# SAMV71_Xplained_Ultra_MCU_Peripherals.net
KiCad netlist of a schematic drawn in Altium Designer
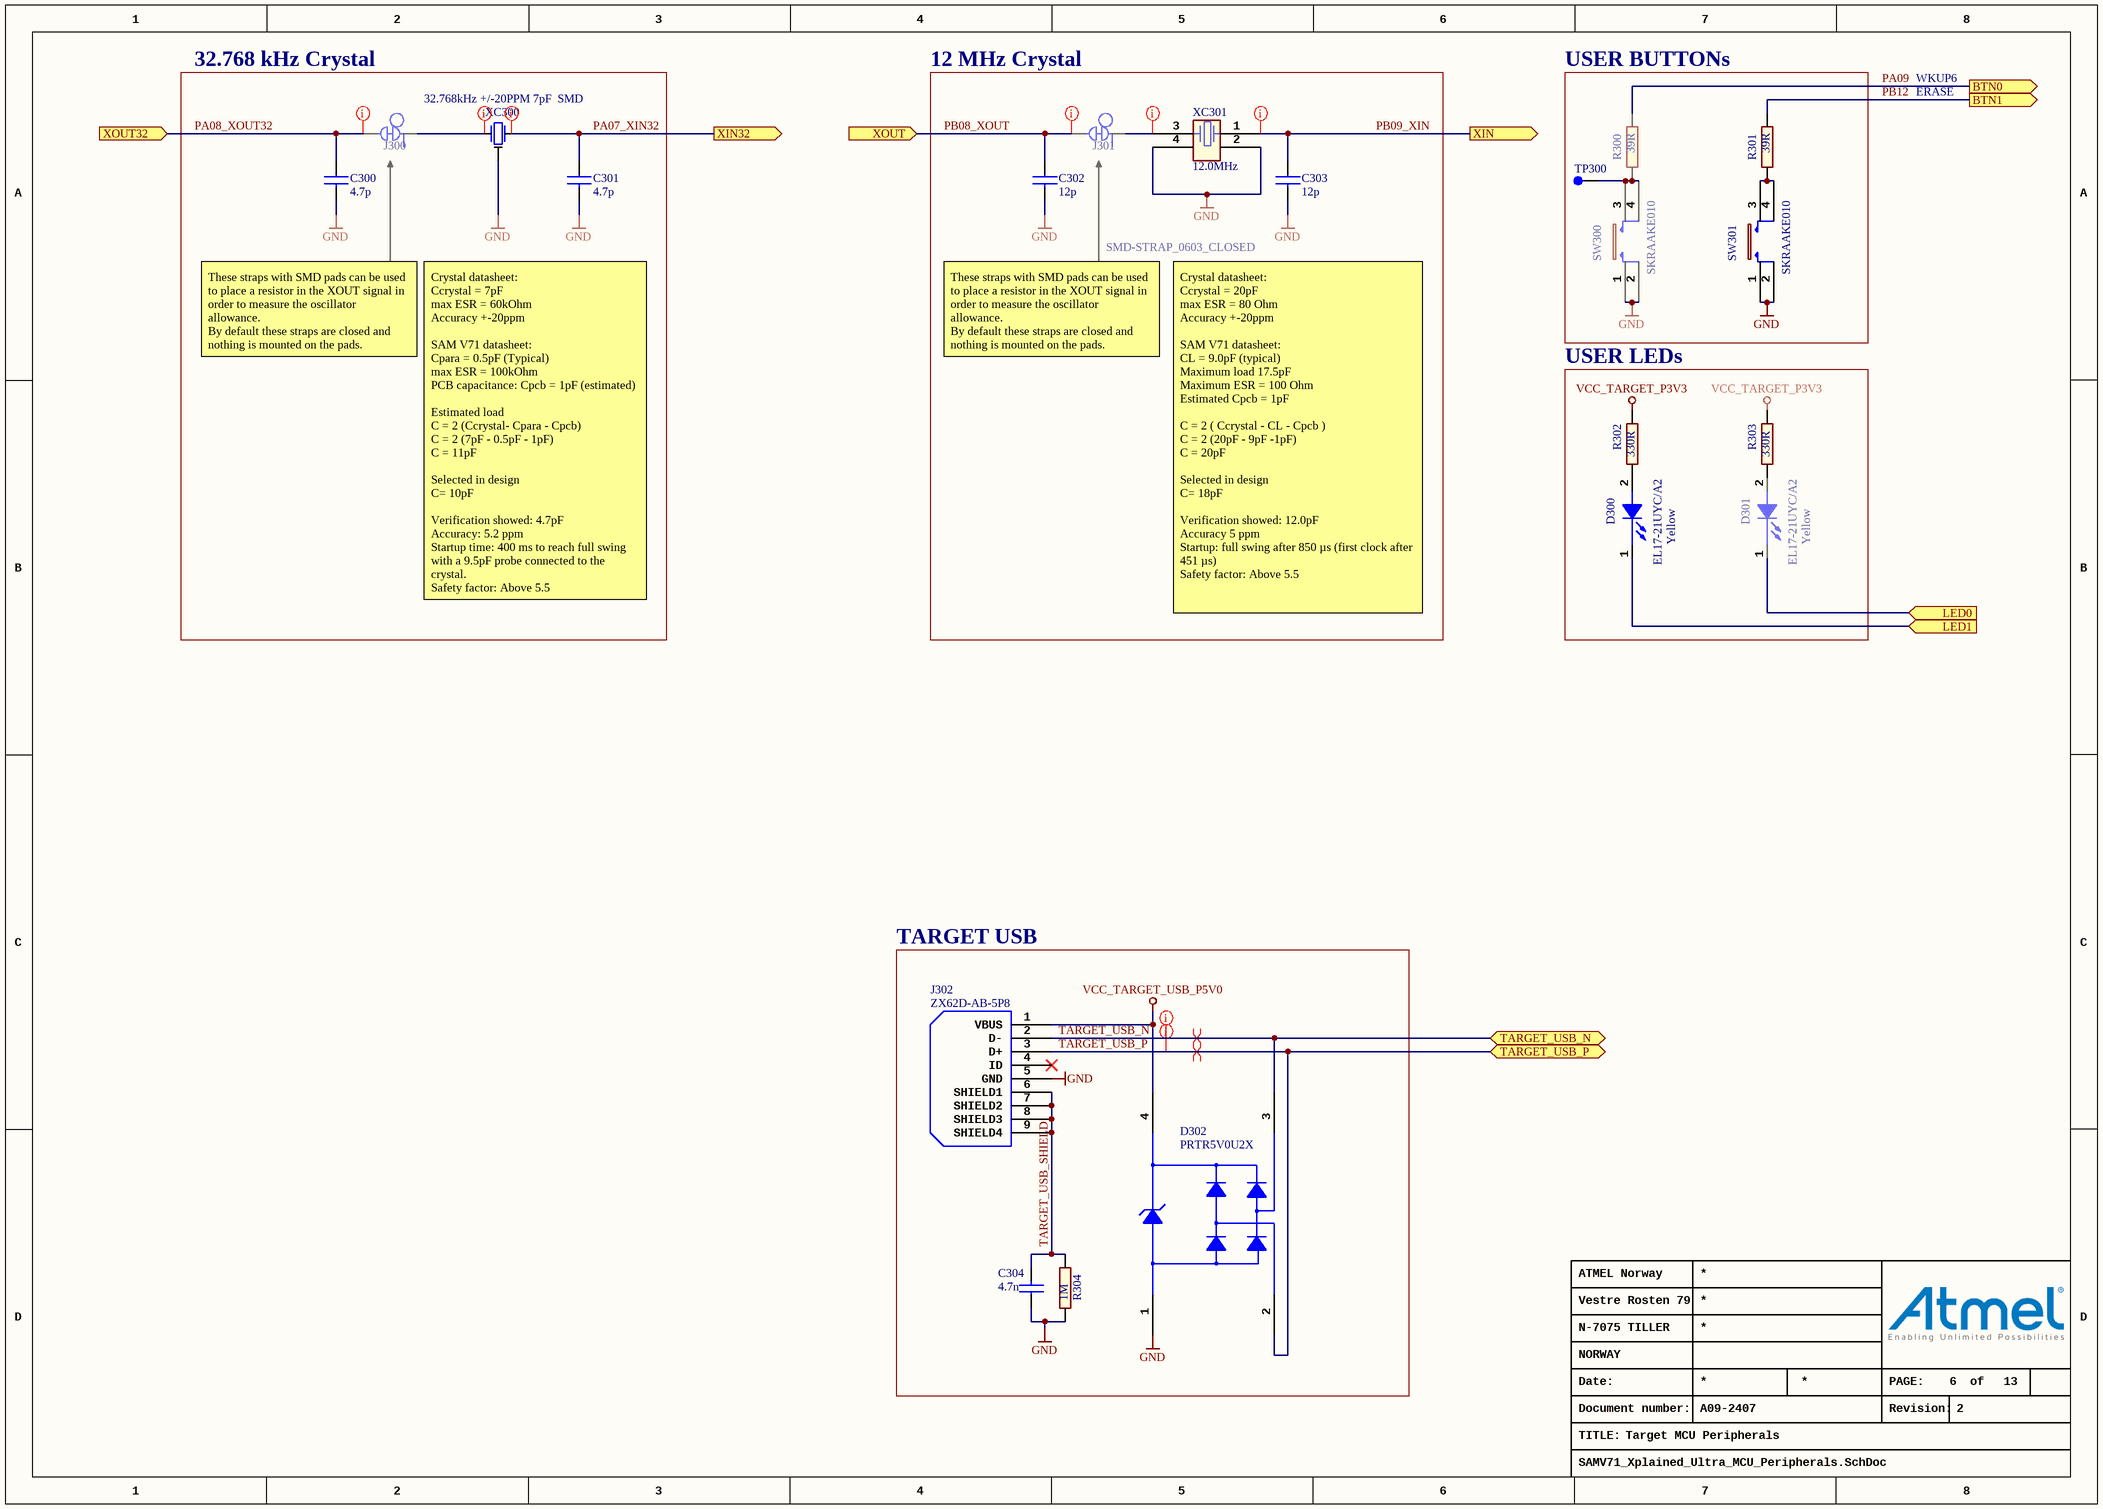
[diagram p0: SAMV71_Xplained_Ultra_MCU_Peripherals.SchDoc]

(export (version "E")
  (design (tool "Eeschema 10.0.6"))
  (components
    (comp (ref "C300")
      (value "4.7p")
      (footprint "AP1-00001")
      (description "Ceramic capacitor, SMD 0402, NP0, 50V, +/-0.25pF")
      (fields (field (name "TOLERANCE") "50V, +/-0.25pF") (field (name "Comment") "CAP-NONPOL"))
      (libsource (lib "AltiumDbLib") (part "CAP-NONPOL"))
    )
    (comp (ref "C301")
      (value "4.7p")
      (footprint "AP1-00001")
      (description "Ceramic capacitor, SMD 0402, NP0, 50V, +/-0.25pF")
      (fields (field (name "TOLERANCE") "50V, +/-0.25pF") (field (name "Comment") "CAP-NONPOL"))
      (libsource (lib "AltiumDbLib") (part "CAP-NONPOL"))
    )
    (comp (ref "C302")
      (value "12p")
      (footprint "AP1-00001")
      (description "Ceramic capacitor, SMD 0402, NP0, 50V, +/-5%")
      (fields (field (name "TOLERANCE") "50V, +/-5%") (field (name "Comment") "CAP-NONPOL"))
      (libsource (lib "AltiumDbLib") (part "CAP-NONPOL"))
    )
    (comp (ref "C303")
      (value "12p")
      (footprint "AP1-00001")
      (description "Ceramic capacitor, SMD 0402, NP0, 50V, +/-5%")
      (fields (field (name "TOLERANCE") "50V, +/-5%") (field (name "Comment") "CAP-NONPOL"))
      (libsource (lib "AltiumDbLib") (part "CAP-NONPOL"))
    )
    (comp (ref "C304")
      (value "4.7n")
      (footprint "AP1-00053")
      (description "Ceramic capacitor, SMD 0402, X7R, 25V, +/-10%")
      (fields (field (name "TOLERANCE") "25V, +/-10%") (field (name "Comment") "CAP-NONPOL"))
      (libsource (lib "AltiumDbLib") (part "CAP-NONPOL"))
    )
    (comp (ref "D300")
      (value "Yellow")
      (footprint "AP4-00013")
      (description "LED, Yellow, Wave length=591nm, SMD 0805, ±70°")
      (fields
        (field (name "ALTIUM_VALUE") "EL17-21UYC/A2")
        (field (name "MANUFACTURER") "Everlight")
        (field (name "MPN") "17-21UYC/S530-A3/TR8")
      )
      (libsource (lib "AltiumDbLib") (part "LED_12"))
    )
    (comp (ref "D301")
      (value "Yellow")
      (footprint "AP4-00013")
      (description "LED, Yellow, Wave length=591nm, SMD 0805, ±70°")
      (fields
        (field (name "ALTIUM_VALUE") "EL17-21UYC/A2")
        (field (name "MANUFACTURER") "Everlight")
        (field (name "MPN") "17-21UYC/S530-A3/TR8")
      )
      (libsource (lib "AltiumDbLib") (part "LED_12"))
    )
    (comp (ref "D302")
      (value "PRTR5V0U2X")
      (footprint "AP4-00001")
      (description "Double rail-to-rail USB ESD protection diode")
      (fields (field (name "MANUFACTURER") "Philips"))
      (libsource (lib "AltiumDbLib") (part "PRTR5V0U2X"))
    )
    (comp (ref "J300")
      (value "~")
      (footprint "AP9-00044")
      (description "Default closed SMD strap, 0603 size")
      (libsource (lib "AltiumDbLib") (part "SMD-STRAP_CLOSED"))
    )
    (comp (ref "J301")
      (value "SMD-STRAP_0603_CLOSED")
      (footprint "AP9-00044")
      (description "Default closed SMD strap, 0603 size")
      (libsource (lib "AltiumDbLib") (part "SMD-STRAP_CLOSED"))
    )
    (comp (ref "J302")
      (value "ZX62D-AB-5P8")
      (footprint "AP8-00852")
      (description "Micro USB AB Connector, Standard SMT + DIP")
      (fields (field (name "Comment") "2,000 pieces per reel"))
      (libsource (lib "AltiumDbLib") (part "USB_AB"))
    )
    (comp (ref "R300")
      (value "39R")
      (footprint "AP2-00011")
      (description "Thick film resistor, SMD 0402, 1/16W, 1%")
      (fields (field (name "TOLERANCE") "1 %") (field (name "Comment") "R2"))
      (libsource (lib "") (part "R2_1"))
    )
    (comp (ref "R301")
      (value "39R")
      (footprint "AP2-00011")
      (description "Thick film resistor, SMD 0402, 1/16W, 1%")
      (fields (field (name "TOLERANCE") "1 %") (field (name "Comment") "R2"))
      (libsource (lib "") (part "R2_1"))
    )
    (comp (ref "R302")
      (value "330R")
      (footprint "AP2-00000")
      (description "Thick film resistor, SMD 0402, 1/16W, 1%")
      (fields (field (name "TOLERANCE") "1 %") (field (name "Comment") "R2"))
      (libsource (lib "AltiumDbLib") (part "R2"))
    )
    (comp (ref "R303")
      (value "330R")
      (footprint "AP2-00000")
      (description "Thick film resistor, SMD 0402, 1/16W, 1%")
      (fields (field (name "TOLERANCE") "1 %") (field (name "Comment") "R2"))
      (libsource (lib "AltiumDbLib") (part "R2"))
    )
    (comp (ref "R304")
      (value "1M")
      (footprint "AP2-00011")
      (description "Thick film resistor, SMD 0402, 1/16W, 1%")
      (fields (field (name "TOLERANCE") "1 %") (field (name "MANUFACTURER") "KOA"))
      (libsource (lib "") (part "R2_1"))
    )
    (comp (ref "SW300")
      (value "SKRAAKE010")
      (footprint "AP8-00137")
      (description "6.2x6.2 mm SMD tact switch, same as A08-0091 but less force is needed")
      (fields
        (field (name "MANUFACTURER") "ALPS")
        (field (name "Comment") "Can be ordered in low volumes from Mouser")
      )
      (libsource (lib "AltiumDbLib") (part "PUSHBUTTON1"))
    )
    (comp (ref "SW301")
      (value "SKRAAKE010")
      (footprint "AP8-00137")
      (description "6.2x6.2 mm SMD tact switch, same as A08-0091 but less force is needed")
      (fields
        (field (name "MANUFACTURER") "ALPS")
        (field (name "Comment") "Can be ordered in low volumes from Mouser")
      )
      (libsource (lib "AltiumDbLib") (part "PUSHBUTTON1"))
    )
    (comp (ref "TP300")
      (value "TESTPOINT")
      (footprint "AP8-00010")
      (description "Single SMD testpad")
      (libsource (lib "AltiumDbLib") (part "TESTPOINT"))
    )
    (comp (ref "XC300")
      (value "32.768kHz +/-20PPM 7pF  SMD")
      (footprint "AP7-00044")
      (description "32k768 crystal, +-20ppm, CL=7pF, max ESR 60kOhm, SMD")
      (fields (field (name "TOLERANCE") "+/- 20 PPM") (field (name "MANUFACTURER") "Micro Crystal"))
      (libsource (lib "AltiumDbLib") (part "CRYSTAL_2P_metal"))
    )
    (comp (ref "XC301")
      (value "12.0MHz")
      (footprint "AP7-00039")
      (description "Fox FQ5032B 12.0MHz SMD crystal 738B-12")
      (fields (field (name "TOLERANCE") "30PPM") (field (name "MANUFACTURER") "Fox  Electronics"))
      (libsource (lib "AltiumDbLib") (part "CRYSTAL1324"))
    )
  )
  (nets
    (net (code "1") (name "/LED0") (class "Default")
      (node (ref "D301") (pin "1") (pinfunction "CATHODE_1") (pintype "passive"))
    )
    (net (code "2") (name "/LED1") (class "Default")
      (node (ref "D300") (pin "1") (pinfunction "CATHODE_1") (pintype "passive"))
    )
    (net (code "3") (name "/PA07_XIN32") (class "Default")
      (node (ref "C301") (pin "1") (pinfunction "1_1") (pintype "passive"))
      (node (ref "XC300") (pin "2") (pinfunction "2_2") (pintype "passive"))
    )
    (net (code "4") (name "/PA08_XOUT32") (class "Default")
      (node (ref "C300") (pin "1") (pinfunction "1_1") (pintype "passive"))
      (node (ref "J300") (pin "2") (pinfunction "2_2") (pintype "passive"))
    )
    (net (code "5") (name "/PA09") (class "Default")
      (node (ref "R300") (pin "2") (pinfunction "2_2") (pintype "passive"))
    )
    (net (code "6") (name "/PB08_XOUT") (class "Default")
      (node (ref "C302") (pin "1") (pinfunction "1_1") (pintype "passive"))
      (node (ref "J301") (pin "2") (pinfunction "2_2") (pintype "passive"))
    )
    (net (code "7") (name "/PB09_XIN") (class "Default")
      (node (ref "C303") (pin "1") (pinfunction "1_1") (pintype "passive"))
      (node (ref "XC301") (pin "1") (pinfunction "1_1") (pintype "passive"))
    )
    (net (code "8") (name "/PB12") (class "Default")
      (node (ref "R301") (pin "2") (pinfunction "2_2") (pintype "passive"))
    )
    (net (code "9") (name "/TARGET_USB_N") (class "Default")
      (node (ref "D302") (pin "3") (pinfunction "I/O_2_3") (pintype "passive"))
      (node (ref "J302") (pin "2") (pinfunction "D-_2") (pintype "passive"))
    )
    (net (code "10") (name "/TARGET_USB_P") (class "Default")
      (node (ref "D302") (pin "2") (pinfunction "I/O_1_2") (pintype "passive"))
      (node (ref "J302") (pin "3") (pinfunction "D+_3") (pintype "passive"))
    )
    (net (code "11") (name "/TARGET_USB_SHIELD") (class "Default")
      (node (ref "C304") (pin "2") (pinfunction "2_2") (pintype "passive"))
      (node (ref "J302") (pin "6") (pinfunction "SHIELD1_6") (pintype "passive"))
      (node (ref "J302") (pin "7") (pinfunction "SHIELD2_7") (pintype "passive"))
      (node (ref "J302") (pin "8") (pinfunction "SHIELD3_8") (pintype "passive"))
      (node (ref "J302") (pin "9") (pinfunction "SHIELD4_9") (pintype "passive"))
      (node (ref "R304") (pin "2") (pinfunction "2_2") (pintype "passive"))
    )
    (net (code "12") (name "GND") (class "Default")
      (node (ref "C300") (pin "2") (pinfunction "2_2") (pintype "passive"))
      (node (ref "C301") (pin "2") (pinfunction "2_2") (pintype "passive"))
      (node (ref "C302") (pin "2") (pinfunction "2_2") (pintype "passive"))
      (node (ref "C303") (pin "2") (pinfunction "2_2") (pintype "passive"))
      (node (ref "C304") (pin "1") (pinfunction "1_1") (pintype "passive"))
      (node (ref "D302") (pin "1") (pinfunction "GND_1") (pintype "passive"))
      (node (ref "J302") (pin "5") (pinfunction "GND_5") (pintype "passive"))
      (node (ref "R304") (pin "1") (pinfunction "1_1") (pintype "passive"))
      (node (ref "SW300") (pin "1") (pinfunction "1_1") (pintype "passive"))
      (node (ref "SW300") (pin "2") (pinfunction "2_2") (pintype "passive"))
      (node (ref "SW301") (pin "1") (pinfunction "1_1") (pintype "passive"))
      (node (ref "SW301") (pin "2") (pinfunction "2_2") (pintype "passive"))
      (node (ref "XC300") (pin "3") (pinfunction "3_3") (pintype "passive"))
      (node (ref "XC301") (pin "2") (pinfunction "2_2") (pintype "passive"))
      (node (ref "XC301") (pin "4") (pinfunction "4_4") (pintype "passive"))
    )
    (net (code "13") (name "Net-(D300-ANODE)") (class "Default")
      (node (ref "D300") (pin "2") (pinfunction "ANODE_2") (pintype "passive"))
      (node (ref "R302") (pin "1") (pinfunction "1_1") (pintype "passive"))
    )
    (net (code "14") (name "Net-(D301-ANODE)") (class "Default")
      (node (ref "D301") (pin "2") (pinfunction "ANODE_2") (pintype "passive"))
      (node (ref "R303") (pin "1") (pinfunction "1_1") (pintype "passive"))
    )
    (net (code "15") (name "Net-(J300-Pad1)") (class "Default")
      (node (ref "J300") (pin "1") (pinfunction "1_1") (pintype "passive"))
      (node (ref "XC300") (pin "1") (pinfunction "1_1") (pintype "passive"))
    )
    (net (code "16") (name "Net-(J301-Pad1)") (class "Default")
      (node (ref "J301") (pin "1") (pinfunction "1_1") (pintype "passive"))
      (node (ref "XC301") (pin "3") (pinfunction "3_3") (pintype "passive"))
    )
    (net (code "17") (name "Net-(R300-Pad1)") (class "Default")
      (node (ref "R300") (pin "1") (pinfunction "1_1") (pintype "passive"))
      (node (ref "SW300") (pin "3") (pinfunction "3_3") (pintype "passive"))
      (node (ref "SW300") (pin "4") (pinfunction "4_4") (pintype "passive"))
      (node (ref "TP300") (pin "1") (pinfunction "1_1") (pintype "passive"))
    )
    (net (code "18") (name "Net-(R301-Pad1)") (class "Default")
      (node (ref "R301") (pin "1") (pinfunction "1_1") (pintype "passive"))
      (node (ref "SW301") (pin "3") (pinfunction "3_3") (pintype "passive"))
      (node (ref "SW301") (pin "4") (pinfunction "4_4") (pintype "passive"))
    )
    (net (code "19") (name "VCC_TARGET_P3V3") (class "Default")
      (node (ref "R302") (pin "2") (pinfunction "2_2") (pintype "passive"))
      (node (ref "R303") (pin "2") (pinfunction "2_2") (pintype "passive"))
    )
    (net (code "20") (name "VCC_TARGET_USB_P5V0") (class "Default")
      (node (ref "D302") (pin "4") (pinfunction "VCC_4") (pintype "passive"))
      (node (ref "J302") (pin "1") (pinfunction "VBUS_1") (pintype "passive"))
    )
    (net (code "21") (name "unconnected-(J302-ID-Pad4)") (class "Default")
      (node (ref "J302") (pin "4") (pinfunction "ID_4") (pintype "passive+no_connect"))
    )
  )
)
